# SD_CARD.net
KiCad netlist of a schematic drawn in Altium Designer
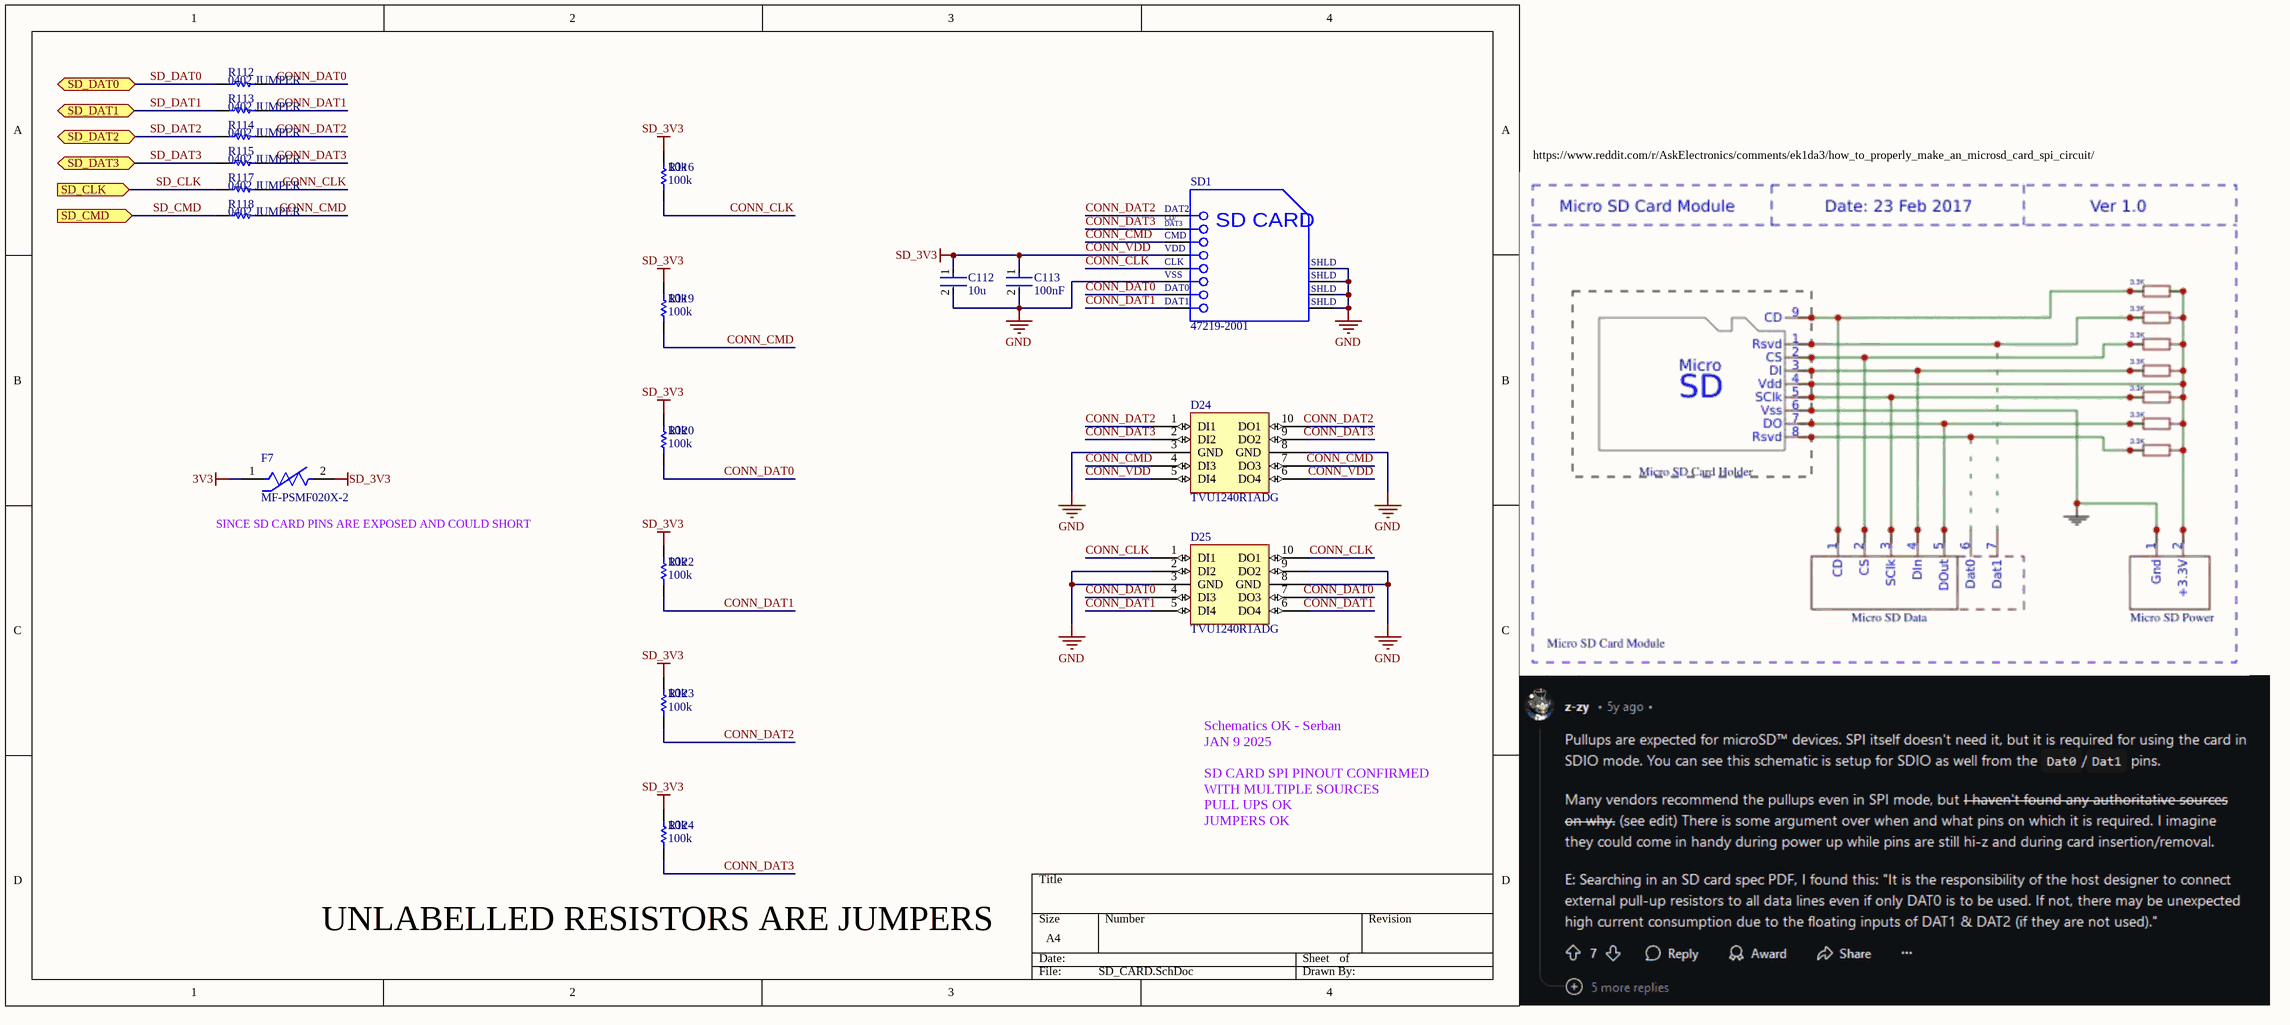
[diagram p0: SD_CARD.SchDoc]

(export (version "E")
  (design (tool "Eeschema 10.0.6"))
  (components
    (comp (ref "C112")
      (value "10u")
      (footprint "FP-0402-L_1_0_0_05-W_0_5-IPC_A")
      (description "LARGE PADS, 0402 CAP, CHANGE COMMENT TO MATCH REAL P/N")
      (libsource (lib "Space Concordia") (part "b4654b650e69147ec39a6b967a45e02"))
    )
    (comp (ref "C113")
      (value "100nF")
      (footprint "FP-0402-L_1_0_0_05-W_0_5-IPC_A")
      (description "LARGE PADS, 0402 CAP, CHANGE COMMENT TO MATCH REAL P/N")
      (libsource (lib "Space Concordia") (part "b4654b650e69147ec39a6b967a45e02"))
    )
    (comp (ref "D24")
      (value "TVU1240R1ADG")
      (footprint "CAF-50P250X100-10N")
      (libsource (lib "Space Concordia") (part "TVU1240R1ADG-Symbol-1"))
    )
    (comp (ref "D25")
      (value "TVU1240R1ADG")
      (footprint "CAF-50P250X100-10N")
      (libsource (lib "Space Concordia") (part "TVU1240R1ADG-Symbol-1"))
    )
    (comp (ref "F7")
      (value "MF-PSMF020X-2")
      (footprint "FP-MF-PSMF-MFG")
      (description "Polymeric PTC Resettable Fuse 9V 200mA Ih Surface Mount 0805 (2012 Metric), Concave")
      (fields (field (name "MANUFACTURER") "Bourns"))
      (libsource (lib "Altium Content Vault") (part "3b148a6ebabc5fb4d708a66c052d352"))
    )
    (comp (ref "R112")
      (value "0402 JUMPER")
      (footprint "RESC1005X40X25ML05T05")
      (description "READ THE NAME")
      (libsource (lib "Space Concordia") (part "CMP-009-00206-2"))
    )
    (comp (ref "R113")
      (value "0402 JUMPER")
      (footprint "RESC1005X40X25ML05T05")
      (description "READ THE NAME")
      (libsource (lib "Space Concordia") (part "CMP-009-00206-2"))
    )
    (comp (ref "R114")
      (value "0402 JUMPER")
      (footprint "RESC1005X40X25ML05T05")
      (description "READ THE NAME")
      (libsource (lib "Space Concordia") (part "CMP-009-00206-2"))
    )
    (comp (ref "R115")
      (value "0402 JUMPER")
      (footprint "RESC1005X40X25ML05T05")
      (description "READ THE NAME")
      (libsource (lib "Space Concordia") (part "CMP-009-00206-2"))
    )
    (comp (ref "R116")
      (value "100k")
      (footprint "R0603B")
      (description "Resistor")
      (fields (field (name "ALTIUM_VALUE") "10k"))
      (libsource (lib "Space Concordia") (part "Resistor"))
    )
    (comp (ref "R117")
      (value "0402 JUMPER")
      (footprint "RESC1005X40X25ML05T05")
      (description "READ THE NAME")
      (libsource (lib "Space Concordia") (part "CMP-009-00206-2"))
    )
    (comp (ref "R118")
      (value "0402 JUMPER")
      (footprint "RESC1005X40X25ML05T05")
      (description "READ THE NAME")
      (libsource (lib "Space Concordia") (part "CMP-009-00206-2"))
    )
    (comp (ref "R119")
      (value "100k")
      (footprint "R0603B")
      (description "Resistor")
      (fields (field (name "ALTIUM_VALUE") "10k"))
      (libsource (lib "Space Concordia") (part "Resistor"))
    )
    (comp (ref "R120")
      (value "100k")
      (footprint "R0603B")
      (description "Resistor")
      (fields (field (name "ALTIUM_VALUE") "10k"))
      (libsource (lib "Space Concordia") (part "Resistor"))
    )
    (comp (ref "R122")
      (value "100k")
      (footprint "R0603B")
      (description "Resistor")
      (fields (field (name "ALTIUM_VALUE") "10k"))
      (libsource (lib "Space Concordia") (part "Resistor"))
    )
    (comp (ref "R123")
      (value "100k")
      (footprint "R0603B")
      (description "Resistor")
      (fields (field (name "ALTIUM_VALUE") "10k"))
      (libsource (lib "Space Concordia") (part "Resistor"))
    )
    (comp (ref "R124")
      (value "100k")
      (footprint "R0603B")
      (description "Resistor")
      (fields (field (name "ALTIUM_VALUE") "10k"))
      (libsource (lib "Space Concordia") (part "Resistor"))
    )
    (comp (ref "SD1")
      (value "47219-2001")
      (footprint "MOLX-47219-2001-8_V")
      (description "MicroSD Card Connector, Hinge Type, -40 to 85 degC, 8-Pin SMD, RoHS, Tape and Reel")
      (fields (field (name "MANUFACTURER") "Molex"))
      (libsource (lib "Altium Content Vault") (part "CN-SD-8-4S"))
    )
  )
  (nets
    (net (code "1") (name "/CONN_CLK") (class "Default")
      (node (ref "D25") (pin "1") (pinfunction "DI1_1") (pintype "bidirectional"))
      (node (ref "D25") (pin "10") (pinfunction "DO1_10") (pintype "bidirectional"))
      (node (ref "R116") (pin "1") (pinfunction "1_1") (pintype "passive"))
      (node (ref "R117") (pin "2") (pinfunction "2_2") (pintype "passive"))
      (node (ref "SD1") (pin "5") (pinfunction "CLK_5") (pintype "passive"))
    )
    (net (code "2") (name "/CONN_CMD") (class "Default")
      (node (ref "D24") (pin "4") (pinfunction "DI3_4") (pintype "bidirectional"))
      (node (ref "D24") (pin "7") (pinfunction "DO3_7") (pintype "bidirectional"))
      (node (ref "R118") (pin "2") (pinfunction "2_2") (pintype "passive"))
      (node (ref "R119") (pin "1") (pinfunction "1_1") (pintype "passive"))
      (node (ref "SD1") (pin "3") (pinfunction "CMD_3") (pintype "passive"))
    )
    (net (code "3") (name "/CONN_DAT0") (class "Default")
      (node (ref "D25") (pin "4") (pinfunction "DI3_4") (pintype "bidirectional"))
      (node (ref "D25") (pin "7") (pinfunction "DO3_7") (pintype "bidirectional"))
      (node (ref "R112") (pin "2") (pinfunction "2_2") (pintype "passive"))
      (node (ref "R120") (pin "1") (pinfunction "1_1") (pintype "passive"))
      (node (ref "SD1") (pin "7") (pinfunction "DAT0_7") (pintype "passive"))
    )
    (net (code "4") (name "/CONN_DAT1") (class "Default")
      (node (ref "D25") (pin "5") (pinfunction "DI4_5") (pintype "bidirectional"))
      (node (ref "D25") (pin "6") (pinfunction "DO4_6") (pintype "bidirectional"))
      (node (ref "R113") (pin "2") (pinfunction "2_2") (pintype "passive"))
      (node (ref "R122") (pin "1") (pinfunction "1_1") (pintype "passive"))
      (node (ref "SD1") (pin "8") (pinfunction "DAT1_8") (pintype "passive"))
    )
    (net (code "5") (name "/CONN_DAT2") (class "Default")
      (node (ref "D24") (pin "1") (pinfunction "DI1_1") (pintype "bidirectional"))
      (node (ref "D24") (pin "10") (pinfunction "DO1_10") (pintype "bidirectional"))
      (node (ref "R114") (pin "2") (pinfunction "2_2") (pintype "passive"))
      (node (ref "R123") (pin "1") (pinfunction "1_1") (pintype "passive"))
      (node (ref "SD1") (pin "1") (pinfunction "DAT2_1") (pintype "passive"))
    )
    (net (code "6") (name "/CONN_DAT3") (class "Default")
      (node (ref "D24") (pin "2") (pinfunction "DI2_2") (pintype "bidirectional"))
      (node (ref "D24") (pin "9") (pinfunction "DO2_9") (pintype "bidirectional"))
      (node (ref "R115") (pin "2") (pinfunction "2_2") (pintype "passive"))
      (node (ref "R124") (pin "1") (pinfunction "1_1") (pintype "passive"))
      (node (ref "SD1") (pin "2") (pinfunction "CD/DAT3_2") (pintype "passive"))
    )
    (net (code "7") (name "/SD_CLK") (class "Default")
      (node (ref "R117") (pin "1") (pinfunction "1_1") (pintype "passive"))
    )
    (net (code "8") (name "/SD_CMD") (class "Default")
      (node (ref "R118") (pin "1") (pinfunction "1_1") (pintype "passive"))
    )
    (net (code "9") (name "/SD_DAT0") (class "Default")
      (node (ref "R112") (pin "1") (pinfunction "1_1") (pintype "passive"))
    )
    (net (code "10") (name "/SD_DAT1") (class "Default")
      (node (ref "R113") (pin "1") (pinfunction "1_1") (pintype "passive"))
    )
    (net (code "11") (name "/SD_DAT2") (class "Default")
      (node (ref "R114") (pin "1") (pinfunction "1_1") (pintype "passive"))
    )
    (net (code "12") (name "/SD_DAT3") (class "Default")
      (node (ref "R115") (pin "1") (pinfunction "1_1") (pintype "passive"))
    )
    (net (code "13") (name "3V3") (class "Default")
      (node (ref "F7") (pin "1") (pinfunction "1_1") (pintype "passive"))
    )
    (net (code "14") (name "GND") (class "Default")
      (node (ref "C112") (pin "2") (pinfunction "2_2") (pintype "passive"))
      (node (ref "C113") (pin "2") (pinfunction "2_2") (pintype "passive"))
      (node (ref "D24") (pin "3") (pinfunction "GND_3") (pintype "power_in"))
      (node (ref "D24") (pin "8") (pinfunction "GND_8") (pintype "power_in"))
      (node (ref "D25") (pin "2") (pinfunction "DI2_2") (pintype "bidirectional"))
      (node (ref "D25") (pin "3") (pinfunction "GND_3") (pintype "power_in"))
      (node (ref "D25") (pin "8") (pinfunction "GND_8") (pintype "power_in"))
      (node (ref "D25") (pin "9") (pinfunction "DO2_9") (pintype "bidirectional"))
      (node (ref "SD1") (pin "10") (pinfunction "SHLD_10") (pintype "passive"))
      (node (ref "SD1") (pin "11") (pinfunction "SHLD_11") (pintype "passive"))
      (node (ref "SD1") (pin "12") (pinfunction "SHLD_12") (pintype "passive"))
      (node (ref "SD1") (pin "6") (pinfunction "VSS_6") (pintype "passive"))
      (node (ref "SD1") (pin "9") (pinfunction "SHLD_9") (pintype "passive"))
    )
    (net (code "15") (name "SD_3V3") (class "Default")
      (node (ref "C112") (pin "1") (pinfunction "1_1") (pintype "passive"))
      (node (ref "C113") (pin "1") (pinfunction "1_1") (pintype "passive"))
      (node (ref "D24") (pin "5") (pinfunction "DI4_5") (pintype "bidirectional"))
      (node (ref "D24") (pin "6") (pinfunction "DO4_6") (pintype "bidirectional"))
      (node (ref "F7") (pin "2") (pinfunction "2_2") (pintype "passive"))
      (node (ref "R116") (pin "2") (pinfunction "2_2") (pintype "passive"))
      (node (ref "R119") (pin "2") (pinfunction "2_2") (pintype "passive"))
      (node (ref "R120") (pin "2") (pinfunction "2_2") (pintype "passive"))
      (node (ref "R122") (pin "2") (pinfunction "2_2") (pintype "passive"))
      (node (ref "R123") (pin "2") (pinfunction "2_2") (pintype "passive"))
      (node (ref "R124") (pin "2") (pinfunction "2_2") (pintype "passive"))
      (node (ref "SD1") (pin "4") (pinfunction "VDD_4") (pintype "passive"))
    )
  )
)
